# 10x10.net
KiCad netlist of a schematic drawn in Altium Designer
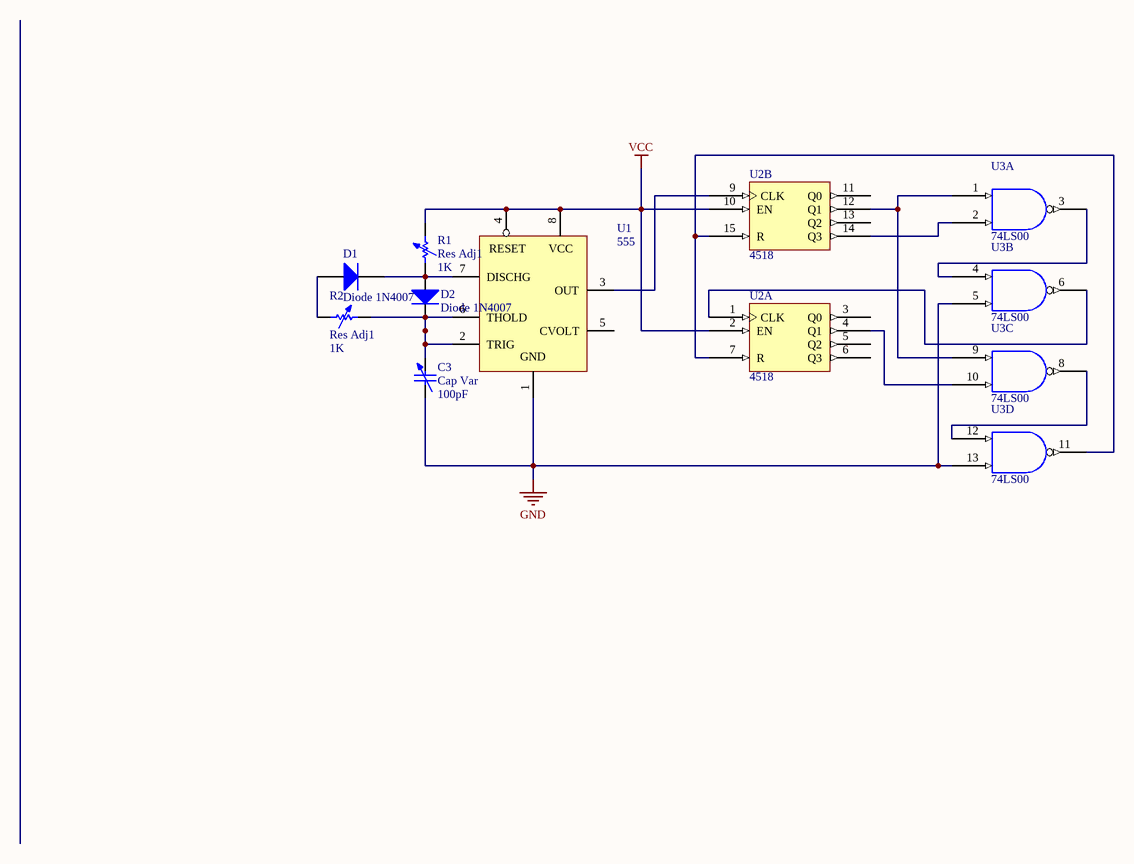
[diagram p0: 10x10.SchDoc]

(export (version "E")
  (design (tool "Eeschema 10.0.6"))
  (components
    (comp (ref "C3")
      (value "Cap Var")
      (footprint "C1210_N")
      (description "Variable or Adjustable Capacitor")
      (fields (field (name "ALTIUM_VALUE") "100pF") (field (name "PUBLISHER") "Altium Limited"))
      (libsource (lib "Miscellaneous Devices") (part "Cap Var"))
    )
    (comp (ref "D1")
      (value "Diode 1N4007")
      (footprint "DO-41")
      (description "1 Amp General Purpose Rectifier")
      (fields (field (name "PUBLISHER") "Altium Limited"))
      (libsource (lib "Miscellaneous Devices") (part "Diode 1N4007"))
    )
    (comp (ref "D2")
      (value "Diode 1N4007")
      (footprint "DO-41")
      (description "1 Amp General Purpose Rectifier")
      (fields (field (name "PUBLISHER") "Altium Limited"))
      (libsource (lib "Miscellaneous Devices") (part "Diode 1N4007"))
    )
    (comp (ref "R1")
      (value "Res Adj1")
      (footprint "AXIAL-0.7")
      (description "Variable Resistor")
      (fields (field (name "ALTIUM_VALUE") "1K") (field (name "PUBLISHER") "Altium Limited"))
      (libsource (lib "Miscellaneous Devices") (part "Res Adj1"))
    )
    (comp (ref "R2")
      (value "Res Adj1")
      (footprint "AXIAL-0.7")
      (description "Variable Resistor")
      (fields (field (name "ALTIUM_VALUE") "1K") (field (name "PUBLISHER") "Altium Limited"))
      (libsource (lib "Miscellaneous Devices") (part "Res Adj1"))
    )
    (comp (ref "U1") (value "555") (description "Timer") (libsource (lib "555") (part "555")))
    (comp (ref "U2") (value "4518") (footprint "DIP-16") (libsource (lib "CD4000系列IC") (part "4518")))
    (comp (ref "U3") (value "74LS00") (footprint "DIP-14") (libsource (lib "TTL74系列IC") (part "74LS00")))
  )
  (nets
    (net (code "1") (name "GND") (class "Default")
      (node (ref "C3") (pin "1") (pinfunction "1_1") (pintype "passive"))
      (node (ref "U1") (pin "1") (pinfunction "GND_1") (pintype "passive"))
      (node (ref "U2") (pin "8") (pinfunction "GND_8") (pintype "power_in"))
      (node (ref "U3") (pin "13") (pintype "input"))
      (node (ref "U3") (pin "5") (pintype "input"))
      (node (ref "U3") (pin "7") (pinfunction "GND_7") (pintype "power_in"))
    )
    (net (code "2") (name "Net-(D1-A)") (class "Default")
      (node (ref "D1") (pin "1") (pinfunction "A_1") (pintype "passive"))
      (node (ref "R2") (pin "1") (pinfunction "1_1") (pintype "passive"))
    )
    (net (code "3") (name "Net-(D1-K)") (class "Default")
      (node (ref "D1") (pin "2") (pinfunction "K_2") (pintype "passive"))
      (node (ref "R1") (pin "1") (pinfunction "1_1") (pintype "passive"))
      (node (ref "U1") (pin "7") (pinfunction "DISCHG_7") (pintype "passive"))
    )
    (net (code "4") (name "Net-(D2-K)") (class "Default")
      (node (ref "C3") (pin "2") (pinfunction "2_2") (pintype "passive"))
      (node (ref "D2") (pin "2") (pinfunction "K_2") (pintype "passive"))
      (node (ref "R2") (pin "2") (pinfunction "2_2") (pintype "passive"))
      (node (ref "U1") (pin "2") (pinfunction "TRIG_2") (pintype "passive"))
      (node (ref "U1") (pin "6") (pinfunction "THOLD_6") (pintype "passive"))
    )
    (net (code "5") (name "Net-(U1-OUT)") (class "Default")
      (node (ref "U1") (pin "3") (pinfunction "OUT_3") (pintype "passive"))
      (node (ref "U2") (pin "9") (pinfunction "CLK_9") (pintype "input"))
    )
    (net (code "6") (name "Net-(U2A-CLK)") (class "Default")
      (node (ref "U2") (pin "1") (pinfunction "CLK_1") (pintype "input"))
      (node (ref "U3") (pin "6") (pintype "output"))
    )
    (net (code "7") (name "Net-(U2A-Q1)") (class "Default")
      (node (ref "U2") (pin "4") (pinfunction "Q1_4") (pintype "output"))
      (node (ref "U3") (pin "10") (pintype "input"))
    )
    (net (code "8") (name "Net-(U2A-R)") (class "Default")
      (node (ref "U2") (pin "15") (pinfunction "R_15") (pintype "input"))
      (node (ref "U2") (pin "7") (pinfunction "R_7") (pintype "input"))
      (node (ref "U3") (pin "11") (pintype "output"))
    )
    (net (code "9") (name "Net-(U2B-Q1)") (class "Default")
      (node (ref "U2") (pin "12") (pinfunction "Q1_12") (pintype "output"))
      (node (ref "U3") (pin "1") (pintype "input"))
      (node (ref "U3") (pin "9") (pintype "input"))
    )
    (net (code "10") (name "Net-(U2B-Q3)") (class "Default")
      (node (ref "U2") (pin "14") (pinfunction "Q3_14") (pintype "output"))
      (node (ref "U3") (pin "2") (pintype "input"))
    )
    (net (code "11") (name "Net-(U3-Pad3)") (class "Default")
      (node (ref "U3") (pin "3") (pintype "output"))
      (node (ref "U3") (pin "4") (pintype "input"))
    )
    (net (code "12") (name "Net-(U3-Pad12)") (class "Default")
      (node (ref "U3") (pin "12") (pintype "input"))
      (node (ref "U3") (pin "8") (pintype "output"))
    )
    (net (code "13") (name "VCC") (class "Default")
      (node (ref "R1") (pin "2") (pinfunction "2_2") (pintype "passive"))
      (node (ref "U1") (pin "4") (pinfunction "RESET_4") (pintype "passive"))
      (node (ref "U1") (pin "8") (pinfunction "VCC_8") (pintype "passive"))
      (node (ref "U2") (pin "10") (pinfunction "EN_10") (pintype "input"))
      (node (ref "U2") (pin "16") (pinfunction "VCC_16") (pintype "power_in"))
      (node (ref "U2") (pin "2") (pinfunction "EN_2") (pintype "input"))
      (node (ref "U3") (pin "14") (pinfunction "VCC_14") (pintype "power_in"))
    )
    (net (code "14") (name "unconnected-(D2-A-Pad1)") (class "Default")
      (node (ref "D2") (pin "1") (pinfunction "A_1") (pintype "passive"))
    )
    (net (code "15") (name "unconnected-(U1-CVOLT-Pad5)") (class "Default")
      (node (ref "U1") (pin "5") (pinfunction "CVOLT_5") (pintype "passive"))
    )
    (net (code "16") (name "unconnected-(U2A-Q0-Pad3)") (class "Default")
      (node (ref "U2") (pin "3") (pinfunction "Q0_3") (pintype "output"))
    )
    (net (code "17") (name "unconnected-(U2A-Q2-Pad5)") (class "Default")
      (node (ref "U2") (pin "5") (pinfunction "Q2_5") (pintype "output"))
    )
    (net (code "18") (name "unconnected-(U2A-Q3-Pad6)") (class "Default")
      (node (ref "U2") (pin "6") (pinfunction "Q3_6") (pintype "output"))
    )
    (net (code "19") (name "unconnected-(U2B-Q0-Pad11)") (class "Default")
      (node (ref "U2") (pin "11") (pinfunction "Q0_11") (pintype "output"))
    )
    (net (code "20") (name "unconnected-(U2B-Q2-Pad13)") (class "Default")
      (node (ref "U2") (pin "13") (pinfunction "Q2_13") (pintype "output"))
    )
  )
)
